# SDC_3.net
KiCad netlist of a schematic drawn in Altium Designer
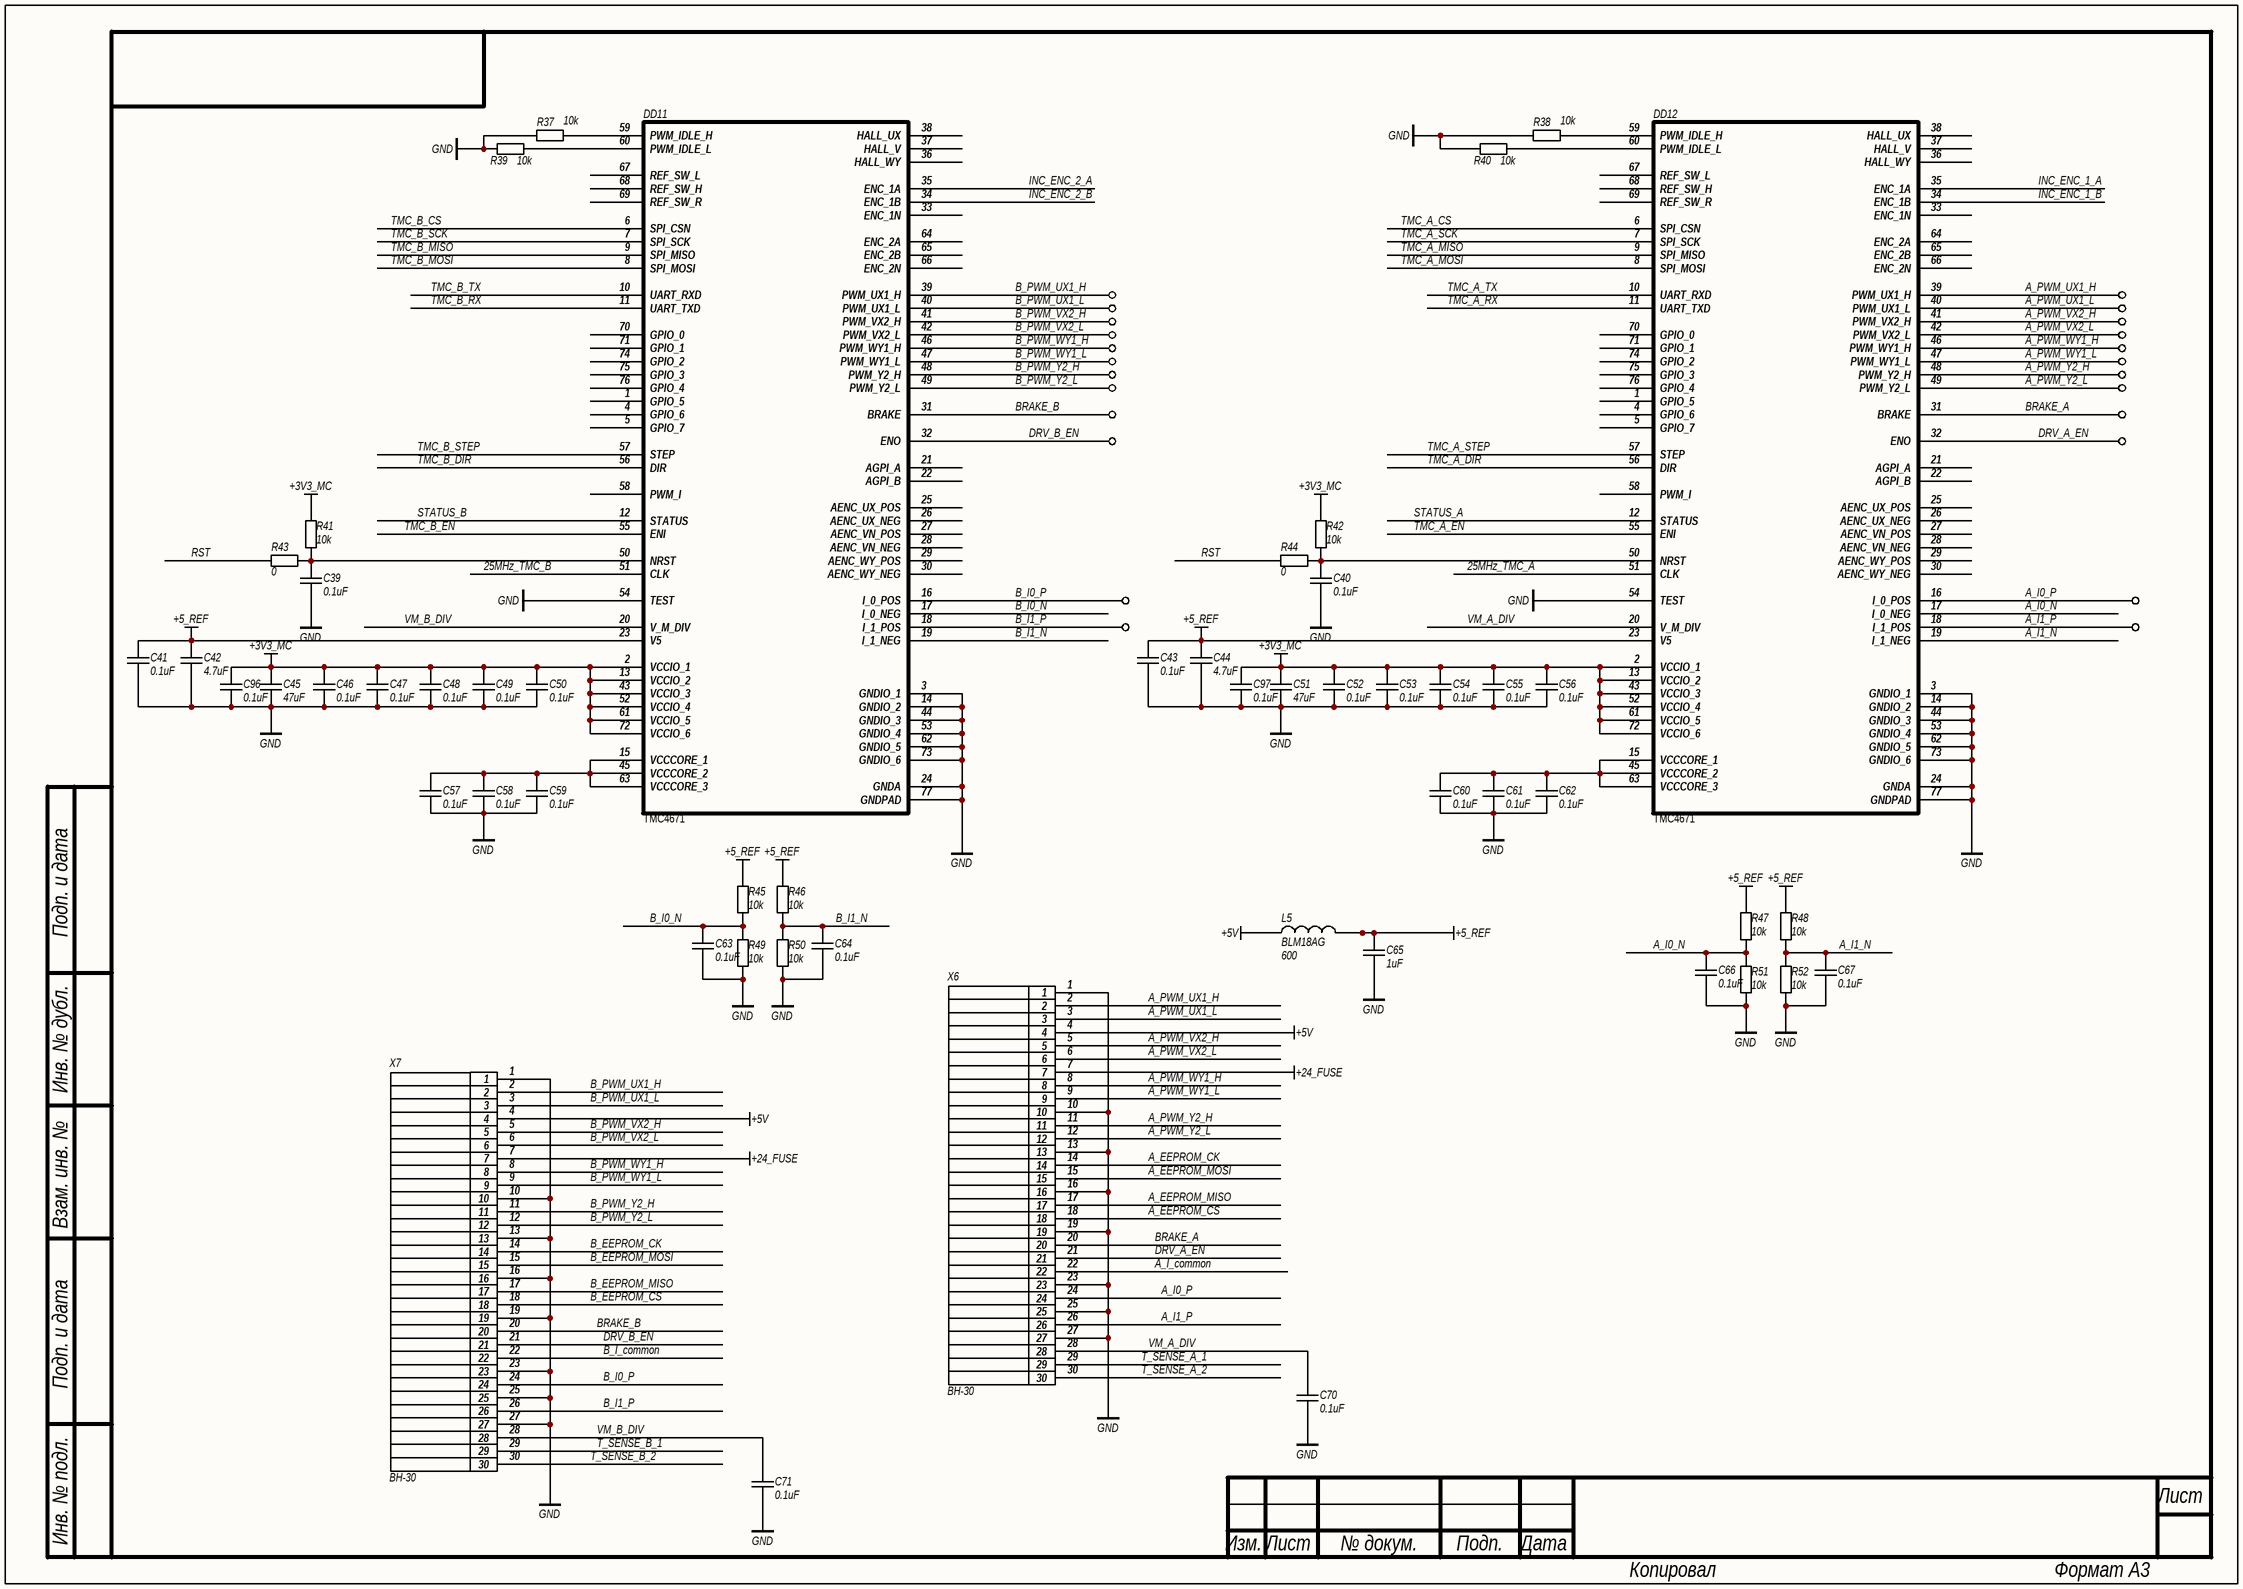
[diagram p0: SDC_3.SchDoc]

(export (version "E")
  (design (tool "Eeschema 10.0.6"))
  (components
    (comp (ref "C39")
      (value "0.1uF")
      (footprint "C0603")
      (description "SMD Capacitor")
      (fields (field (name "MANUFACTURER") "Murata") (field (name "TOLERANCE") "10%"))
      (libsource (lib "VKA") (part "CAP"))
    )
    (comp (ref "C40")
      (value "0.1uF")
      (footprint "C0603")
      (description "SMD Capacitor")
      (fields (field (name "MANUFACTURER") "Murata") (field (name "TOLERANCE") "10%"))
      (libsource (lib "VKA") (part "CAP"))
    )
    (comp (ref "C41")
      (value "0.1uF")
      (footprint "C0603")
      (description "SMD Capacitor")
      (fields (field (name "MANUFACTURER") "Murata") (field (name "TOLERANCE") "10%"))
      (libsource (lib "VKA") (part "CAP"))
    )
    (comp (ref "C42")
      (value "4.7uF")
      (footprint "C0603")
      (description "SMD Capacitor")
      (fields (field (name "MANUFACTURER") "Murata") (field (name "TOLERANCE") "10%"))
      (libsource (lib "VKA") (part "CAP"))
    )
    (comp (ref "C43")
      (value "0.1uF")
      (footprint "C0603")
      (description "SMD Capacitor")
      (fields (field (name "MANUFACTURER") "Murata") (field (name "TOLERANCE") "10%"))
      (libsource (lib "VKA") (part "CAP"))
    )
    (comp (ref "C44")
      (value "4.7uF")
      (footprint "C0603")
      (description "SMD Capacitor")
      (fields (field (name "MANUFACTURER") "Murata") (field (name "TOLERANCE") "10%"))
      (libsource (lib "VKA") (part "CAP"))
    )
    (comp (ref "C45")
      (value "47uF")
      (footprint "C1206")
      (description "SMD Capacitor")
      (fields (field (name "MANUFACTURER") "Murata") (field (name "TOLERANCE") "10%"))
      (libsource (lib "VKA") (part "CAP"))
    )
    (comp (ref "C46")
      (value "0.1uF")
      (footprint "C0603")
      (description "SMD Capacitor")
      (fields (field (name "MANUFACTURER") "Murata") (field (name "TOLERANCE") "10%"))
      (libsource (lib "VKA") (part "CAP"))
    )
    (comp (ref "C47")
      (value "0.1uF")
      (footprint "C0603")
      (description "SMD Capacitor")
      (fields (field (name "MANUFACTURER") "Murata") (field (name "TOLERANCE") "10%"))
      (libsource (lib "VKA") (part "CAP"))
    )
    (comp (ref "C48")
      (value "0.1uF")
      (footprint "C0603")
      (description "SMD Capacitor")
      (fields (field (name "MANUFACTURER") "Murata") (field (name "TOLERANCE") "10%"))
      (libsource (lib "VKA") (part "CAP"))
    )
    (comp (ref "C49")
      (value "0.1uF")
      (footprint "C0603")
      (description "SMD Capacitor")
      (fields (field (name "MANUFACTURER") "Murata") (field (name "TOLERANCE") "10%"))
      (libsource (lib "VKA") (part "CAP"))
    )
    (comp (ref "C50")
      (value "0.1uF")
      (footprint "C0603")
      (description "SMD Capacitor")
      (fields (field (name "MANUFACTURER") "Murata") (field (name "TOLERANCE") "10%"))
      (libsource (lib "VKA") (part "CAP"))
    )
    (comp (ref "C51")
      (value "47uF")
      (footprint "C1206")
      (description "SMD Capacitor")
      (fields (field (name "MANUFACTURER") "Murata") (field (name "TOLERANCE") "10%"))
      (libsource (lib "VKA") (part "CAP"))
    )
    (comp (ref "C52")
      (value "0.1uF")
      (footprint "C0603")
      (description "SMD Capacitor")
      (fields (field (name "MANUFACTURER") "Murata") (field (name "TOLERANCE") "10%"))
      (libsource (lib "VKA") (part "CAP"))
    )
    (comp (ref "C53")
      (value "0.1uF")
      (footprint "C0603")
      (description "SMD Capacitor")
      (fields (field (name "MANUFACTURER") "Murata") (field (name "TOLERANCE") "10%"))
      (libsource (lib "VKA") (part "CAP"))
    )
    (comp (ref "C54")
      (value "0.1uF")
      (footprint "C0603")
      (description "SMD Capacitor")
      (fields (field (name "MANUFACTURER") "Murata") (field (name "TOLERANCE") "10%"))
      (libsource (lib "VKA") (part "CAP"))
    )
    (comp (ref "C55")
      (value "0.1uF")
      (footprint "C0603")
      (description "SMD Capacitor")
      (fields (field (name "MANUFACTURER") "Murata") (field (name "TOLERANCE") "10%"))
      (libsource (lib "VKA") (part "CAP"))
    )
    (comp (ref "C56")
      (value "0.1uF")
      (footprint "C0603")
      (description "SMD Capacitor")
      (fields (field (name "MANUFACTURER") "Murata") (field (name "TOLERANCE") "10%"))
      (libsource (lib "VKA") (part "CAP"))
    )
    (comp (ref "C57")
      (value "0.1uF")
      (footprint "C0603")
      (description "SMD Capacitor")
      (fields (field (name "MANUFACTURER") "Murata") (field (name "TOLERANCE") "10%"))
      (libsource (lib "VKA") (part "CAP"))
    )
    (comp (ref "C58")
      (value "0.1uF")
      (footprint "C0603")
      (description "SMD Capacitor")
      (fields (field (name "MANUFACTURER") "Murata") (field (name "TOLERANCE") "10%"))
      (libsource (lib "VKA") (part "CAP"))
    )
    (comp (ref "C59")
      (value "0.1uF")
      (footprint "C0603")
      (description "SMD Capacitor")
      (fields (field (name "MANUFACTURER") "Murata") (field (name "TOLERANCE") "10%"))
      (libsource (lib "VKA") (part "CAP"))
    )
    (comp (ref "C60")
      (value "0.1uF")
      (footprint "C0603")
      (description "SMD Capacitor")
      (fields (field (name "MANUFACTURER") "Murata") (field (name "TOLERANCE") "10%"))
      (libsource (lib "VKA") (part "CAP"))
    )
    (comp (ref "C61")
      (value "0.1uF")
      (footprint "C0603")
      (description "SMD Capacitor")
      (fields (field (name "MANUFACTURER") "Murata") (field (name "TOLERANCE") "10%"))
      (libsource (lib "VKA") (part "CAP"))
    )
    (comp (ref "C62")
      (value "0.1uF")
      (footprint "C0603")
      (description "SMD Capacitor")
      (fields (field (name "MANUFACTURER") "Murata") (field (name "TOLERANCE") "10%"))
      (libsource (lib "VKA") (part "CAP"))
    )
    (comp (ref "C63")
      (value "0.1uF")
      (footprint "C0603")
      (description "SMD Capacitor")
      (fields (field (name "MANUFACTURER") "Murata") (field (name "TOLERANCE") "10%"))
      (libsource (lib "VKA") (part "CAP"))
    )
    (comp (ref "C64")
      (value "0.1uF")
      (footprint "C0603")
      (description "SMD Capacitor")
      (fields (field (name "MANUFACTURER") "Murata") (field (name "TOLERANCE") "10%"))
      (libsource (lib "VKA") (part "CAP"))
    )
    (comp (ref "C65")
      (value "1uF")
      (footprint "C0603")
      (description "SMD Capacitor")
      (fields (field (name "MANUFACTURER") "Murata") (field (name "TOLERANCE") "10%"))
      (libsource (lib "VKA") (part "CAP"))
    )
    (comp (ref "C66")
      (value "0.1uF")
      (footprint "C0603")
      (description "SMD Capacitor")
      (fields (field (name "MANUFACTURER") "Murata") (field (name "TOLERANCE") "10%"))
      (libsource (lib "VKA") (part "CAP"))
    )
    (comp (ref "C67")
      (value "0.1uF")
      (footprint "C0603")
      (description "SMD Capacitor")
      (fields (field (name "MANUFACTURER") "Murata") (field (name "TOLERANCE") "10%"))
      (libsource (lib "VKA") (part "CAP"))
    )
    (comp (ref "C70")
      (value "0.1uF")
      (footprint "C0603")
      (description "SMD Capacitor")
      (fields (field (name "MANUFACTURER") "Murata") (field (name "TOLERANCE") "10%"))
      (libsource (lib "VKA") (part "CAP"))
    )
    (comp (ref "C71")
      (value "0.1uF")
      (footprint "C0603")
      (description "SMD Capacitor")
      (fields (field (name "MANUFACTURER") "Murata") (field (name "TOLERANCE") "10%"))
      (libsource (lib "VKA") (part "CAP"))
    )
    (comp (ref "C96")
      (value "0.1uF")
      (footprint "C0603")
      (description "SMD Capacitor")
      (fields (field (name "MANUFACTURER") "Murata") (field (name "TOLERANCE") "10%"))
      (libsource (lib "VKA") (part "CAP"))
    )
    (comp (ref "C97")
      (value "0.1uF")
      (footprint "C0603")
      (description "SMD Capacitor")
      (fields (field (name "MANUFACTURER") "Murata") (field (name "TOLERANCE") "10%"))
      (libsource (lib "VKA") (part "CAP"))
    )
    (comp (ref "DD11")
      (value "TMC4671")
      (footprint "QFN76")
      (description "Motion_controller")
      (libsource (lib "VKA") (part "TMC4671"))
    )
    (comp (ref "DD12")
      (value "TMC4671")
      (footprint "QFN76")
      (description "Motion_controller")
      (libsource (lib "VKA") (part "TMC4671"))
    )
    (comp (ref "L5")
      (value "BLM18AG")
      (footprint "R0603")
      (fields (field (name "ALTIUM_VALUE") "600"))
      (libsource (lib "VKA") (part "BLM18AG"))
    )
    (comp (ref "R37")
      (value "10k")
      (footprint "R0603")
      (description "SMD Resistor")
      (fields (field (name "POWER") "0.062 Wt") (field (name "TOLERANCE") "5%"))
      (libsource (lib "VKA") (part "RES"))
    )
    (comp (ref "R38")
      (value "10k")
      (footprint "R0603")
      (description "SMD Resistor")
      (fields (field (name "POWER") "0.062 Wt") (field (name "TOLERANCE") "5%"))
      (libsource (lib "VKA") (part "RES"))
    )
    (comp (ref "R39")
      (value "10k")
      (footprint "R0603")
      (description "SMD Resistor")
      (fields (field (name "POWER") "0.062 Wt") (field (name "TOLERANCE") "5%"))
      (libsource (lib "VKA") (part "RES"))
    )
    (comp (ref "R40")
      (value "10k")
      (footprint "R0603")
      (description "SMD Resistor")
      (fields (field (name "POWER") "0.062 Wt") (field (name "TOLERANCE") "5%"))
      (libsource (lib "VKA") (part "RES"))
    )
    (comp (ref "R41")
      (value "10k")
      (footprint "R0603")
      (description "SMD Resistor")
      (fields (field (name "POWER") "0.062 Wt") (field (name "TOLERANCE") "5%"))
      (libsource (lib "") (part "RES_1"))
    )
    (comp (ref "R42")
      (value "10k")
      (footprint "R0603")
      (description "SMD Resistor")
      (fields (field (name "POWER") "0.062 Wt") (field (name "TOLERANCE") "5%"))
      (libsource (lib "") (part "RES_1"))
    )
    (comp (ref "R43")
      (value "0")
      (footprint "R0603")
      (description "SMD Resistor")
      (fields (field (name "POWER") "0.062 Wt") (field (name "TOLERANCE") "5%"))
      (libsource (lib "VKA") (part "RES"))
    )
    (comp (ref "R44")
      (value "0")
      (footprint "R0603")
      (description "SMD Resistor")
      (fields (field (name "POWER") "0.062 Wt") (field (name "TOLERANCE") "5%"))
      (libsource (lib "VKA") (part "RES"))
    )
    (comp (ref "R45")
      (value "10k")
      (footprint "R0603")
      (description "SMD Resistor")
      (fields (field (name "POWER") "0.062 Wt") (field (name "TOLERANCE") "5%"))
      (libsource (lib "") (part "RES_1"))
    )
    (comp (ref "R46")
      (value "10k")
      (footprint "R0603")
      (description "SMD Resistor")
      (fields (field (name "POWER") "0.062 Wt") (field (name "TOLERANCE") "5%"))
      (libsource (lib "") (part "RES_1"))
    )
    (comp (ref "R47")
      (value "10k")
      (footprint "R0603")
      (description "SMD Resistor")
      (fields (field (name "POWER") "0.062 Wt") (field (name "TOLERANCE") "5%"))
      (libsource (lib "") (part "RES_1"))
    )
    (comp (ref "R48")
      (value "10k")
      (footprint "R0603")
      (description "SMD Resistor")
      (fields (field (name "POWER") "0.062 Wt") (field (name "TOLERANCE") "5%"))
      (libsource (lib "") (part "RES_1"))
    )
    (comp (ref "R49")
      (value "10k")
      (footprint "R0603")
      (description "SMD Resistor")
      (fields (field (name "POWER") "0.062 Wt") (field (name "TOLERANCE") "5%"))
      (libsource (lib "") (part "RES_1"))
    )
    (comp (ref "R50")
      (value "10k")
      (footprint "R0603")
      (description "SMD Resistor")
      (fields (field (name "POWER") "0.062 Wt") (field (name "TOLERANCE") "5%"))
      (libsource (lib "") (part "RES_1"))
    )
    (comp (ref "R51")
      (value "10k")
      (footprint "R0603")
      (description "SMD Resistor")
      (fields (field (name "POWER") "0.062 Wt") (field (name "TOLERANCE") "5%"))
      (libsource (lib "") (part "RES_1"))
    )
    (comp (ref "R52")
      (value "10k")
      (footprint "R0603")
      (description "SMD Resistor")
      (fields (field (name "POWER") "0.062 Wt") (field (name "TOLERANCE") "5%"))
      (libsource (lib "") (part "RES_1"))
    )
    (comp (ref "TP1") (value "Test_point") (footprint "TP1") (libsource (lib "VKA") (part "TP")))
    (comp (ref "TP2") (value "Test_point") (footprint "TP1") (libsource (lib "VKA") (part "TP")))
    (comp (ref "TP3") (value "Test_point") (footprint "TP1") (libsource (lib "VKA") (part "TP")))
    (comp (ref "TP4") (value "Test_point") (footprint "TP1") (libsource (lib "VKA") (part "TP")))
    (comp (ref "TP5") (value "Test_point") (footprint "TP1") (libsource (lib "VKA") (part "TP")))
    (comp (ref "TP6") (value "Test_point") (footprint "TP1") (libsource (lib "VKA") (part "TP")))
    (comp (ref "TP7") (value "Test_point") (footprint "TP1") (libsource (lib "VKA") (part "TP")))
    (comp (ref "TP8") (value "Test_point") (footprint "TP1") (libsource (lib "VKA") (part "TP")))
    (comp (ref "TP9") (value "Test_point") (footprint "TP1") (libsource (lib "VKA") (part "TP")))
    (comp (ref "TP10") (value "Test_point") (footprint "TP1") (libsource (lib "VKA") (part "TP")))
    (comp (ref "TP11") (value "Test_point") (footprint "TP1") (libsource (lib "VKA") (part "TP")))
    (comp (ref "TP12") (value "Test_point") (footprint "TP1") (libsource (lib "VKA") (part "TP")))
    (comp (ref "TP13") (value "Test_point") (footprint "TP1") (libsource (lib "VKA") (part "TP")))
    (comp (ref "TP14") (value "Test_point") (footprint "TP1") (libsource (lib "VKA") (part "TP")))
    (comp (ref "TP15") (value "Test_point") (footprint "TP1") (libsource (lib "VKA") (part "TP")))
    (comp (ref "TP16") (value "Test_point") (footprint "TP1") (libsource (lib "VKA") (part "TP")))
    (comp (ref "TP17") (value "Test_point") (footprint "TP1") (libsource (lib "VKA") (part "TP")))
    (comp (ref "TP18") (value "Test_point") (footprint "TP1") (libsource (lib "VKA") (part "TP")))
    (comp (ref "TP19") (value "Test_point") (footprint "TP1") (libsource (lib "VKA") (part "TP")))
    (comp (ref "TP20") (value "Test_point") (footprint "TP1") (libsource (lib "VKA") (part "TP")))
    (comp (ref "TP21") (value "Test_point") (footprint "TP1") (libsource (lib "VKA") (part "TP")))
    (comp (ref "TP22") (value "Test_point") (footprint "TP1") (libsource (lib "VKA") (part "TP")))
    (comp (ref "TP23") (value "Test_point") (footprint "TP1") (libsource (lib "VKA") (part "TP")))
    (comp (ref "TP24") (value "Test_point") (footprint "TP1") (libsource (lib "VKA") (part "TP")))
    (comp (ref "X6")
      (value "BH-30")
      (footprint "IDC-30(BH-30)")
      (libsource (lib "VKA") (part "IDC15x2_GOST"))
    )
    (comp (ref "X7")
      (value "BH-30")
      (footprint "IDC-30(BH-30)")
      (libsource (lib "VKA") (part "IDC15x2_GOST"))
    )
  )
  (nets
    (net (code "1") (name "+3V3_MC") (class "Default")
      (node (ref "C45") (pin "2") (pinfunction "2_2") (pintype "passive"))
      (node (ref "C46") (pin "2") (pinfunction "2_2") (pintype "passive"))
      (node (ref "C47") (pin "2") (pinfunction "2_2") (pintype "passive"))
      (node (ref "C48") (pin "2") (pinfunction "2_2") (pintype "passive"))
      (node (ref "C49") (pin "2") (pinfunction "2_2") (pintype "passive"))
      (node (ref "C50") (pin "2") (pinfunction "2_2") (pintype "passive"))
      (node (ref "C51") (pin "2") (pinfunction "2_2") (pintype "passive"))
      (node (ref "C52") (pin "2") (pinfunction "2_2") (pintype "passive"))
      (node (ref "C53") (pin "2") (pinfunction "2_2") (pintype "passive"))
      (node (ref "C54") (pin "2") (pinfunction "2_2") (pintype "passive"))
      (node (ref "C55") (pin "2") (pinfunction "2_2") (pintype "passive"))
      (node (ref "C56") (pin "2") (pinfunction "2_2") (pintype "passive"))
      (node (ref "C96") (pin "2") (pinfunction "2_2") (pintype "passive"))
      (node (ref "C97") (pin "2") (pinfunction "2_2") (pintype "passive"))
      (node (ref "DD11") (pin "13") (pinfunction "VCCIO_2_13") (pintype "passive"))
      (node (ref "DD11") (pin "2") (pinfunction "VCCIO_1_2") (pintype "passive"))
      (node (ref "DD11") (pin "43") (pinfunction "VCCIO_3_43") (pintype "passive"))
      (node (ref "DD11") (pin "52") (pinfunction "VCCIO_4_52") (pintype "passive"))
      (node (ref "DD11") (pin "61") (pinfunction "VCCIO_5_61") (pintype "passive"))
      (node (ref "DD11") (pin "72") (pinfunction "VCCIO_6_72") (pintype "passive"))
      (node (ref "DD12") (pin "13") (pinfunction "VCCIO_2_13") (pintype "passive"))
      (node (ref "DD12") (pin "2") (pinfunction "VCCIO_1_2") (pintype "passive"))
      (node (ref "DD12") (pin "43") (pinfunction "VCCIO_3_43") (pintype "passive"))
      (node (ref "DD12") (pin "52") (pinfunction "VCCIO_4_52") (pintype "passive"))
      (node (ref "DD12") (pin "61") (pinfunction "VCCIO_5_61") (pintype "passive"))
      (node (ref "DD12") (pin "72") (pinfunction "VCCIO_6_72") (pintype "passive"))
      (node (ref "R41") (pin "2") (pinfunction "2_2") (pintype "passive"))
      (node (ref "R42") (pin "2") (pinfunction "2_2") (pintype "passive"))
    )
    (net (code "2") (name "+5V") (class "Default")
      (node (ref "L5") (pin "1") (pinfunction "1_1") (pintype "passive"))
      (node (ref "X6") (pin "4") (pinfunction "4_4") (pintype "passive"))
      (node (ref "X7") (pin "4") (pinfunction "4_4") (pintype "passive"))
    )
    (net (code "3") (name "+5_REF") (class "Default")
      (node (ref "C41") (pin "2") (pinfunction "2_2") (pintype "passive"))
      (node (ref "C42") (pin "2") (pinfunction "2_2") (pintype "passive"))
      (node (ref "C43") (pin "2") (pinfunction "2_2") (pintype "passive"))
      (node (ref "C44") (pin "2") (pinfunction "2_2") (pintype "passive"))
      (node (ref "C65") (pin "2") (pinfunction "2_2") (pintype "passive"))
      (node (ref "DD11") (pin "23") (pinfunction "V5_23") (pintype "passive"))
      (node (ref "DD12") (pin "23") (pinfunction "V5_23") (pintype "passive"))
      (node (ref "L5") (pin "2") (pinfunction "2_2") (pintype "passive"))
      (node (ref "R45") (pin "2") (pinfunction "2_2") (pintype "passive"))
      (node (ref "R46") (pin "2") (pinfunction "2_2") (pintype "passive"))
      (node (ref "R47") (pin "2") (pinfunction "2_2") (pintype "passive"))
      (node (ref "R48") (pin "2") (pinfunction "2_2") (pintype "passive"))
    )
    (net (code "4") (name "+24_FUSE") (class "Default")
      (node (ref "X6") (pin "7") (pinfunction "7_7") (pintype "passive"))
      (node (ref "X7") (pin "7") (pinfunction "7_7") (pintype "passive"))
    )
    (net (code "5") (name "/25MHz_TMC_A") (class "Default")
      (node (ref "DD12") (pin "51") (pinfunction "CLK_51") (pintype "passive"))
    )
    (net (code "6") (name "/25MHz_TMC_B") (class "Default")
      (node (ref "DD11") (pin "51") (pinfunction "CLK_51") (pintype "passive"))
    )
    (net (code "7") (name "/A_EEPROM_CK") (class "Default")
      (node (ref "X6") (pin "14") (pinfunction "14_14") (pintype "passive"))
    )
    (net (code "8") (name "/A_EEPROM_CS") (class "Default")
      (node (ref "X6") (pin "18") (pinfunction "18_18") (pintype "passive"))
    )
    (net (code "9") (name "/A_EEPROM_MISO") (class "Default")
      (node (ref "X6") (pin "17") (pinfunction "17_17") (pintype "passive"))
    )
    (net (code "10") (name "/A_EEPROM_MOSI") (class "Default")
      (node (ref "X6") (pin "15") (pinfunction "15_15") (pintype "passive"))
    )
    (net (code "11") (name "/A_I0_N") (class "Default")
      (node (ref "C66") (pin "2") (pinfunction "2_2") (pintype "passive"))
      (node (ref "DD12") (pin "17") (pinfunction "I_0_NEG_17") (pintype "passive"))
      (node (ref "R47") (pin "1") (pinfunction "1_1") (pintype "passive"))
      (node (ref "R51") (pin "2") (pinfunction "2_2") (pintype "passive"))
    )
    (net (code "12") (name "/A_I0_P") (class "Default")
      (node (ref "DD12") (pin "16") (pinfunction "I_0_POS_16") (pintype "passive"))
      (node (ref "TP23") (pin "1") (pinfunction "1_1") (pintype "passive"))
      (node (ref "X6") (pin "24") (pinfunction "24_24") (pintype "passive"))
    )
    (net (code "13") (name "/A_I1_N") (class "Default")
      (node (ref "C67") (pin "2") (pinfunction "2_2") (pintype "passive"))
      (node (ref "DD12") (pin "19") (pinfunction "I_1_NEG_19") (pintype "passive"))
      (node (ref "R48") (pin "1") (pinfunction "1_1") (pintype "passive"))
      (node (ref "R52") (pin "2") (pinfunction "2_2") (pintype "passive"))
    )
    (net (code "14") (name "/A_I1_P") (class "Default")
      (node (ref "DD12") (pin "18") (pinfunction "I_1_POS_18") (pintype "passive"))
      (node (ref "TP24") (pin "1") (pinfunction "1_1") (pintype "passive"))
      (node (ref "X6") (pin "26") (pinfunction "26_26") (pintype "passive"))
    )
    (net (code "15") (name "/A_I_common") (class "Default")
      (node (ref "X6") (pin "22") (pinfunction "22_22") (pintype "passive"))
    )
    (net (code "16") (name "/A_PWM_UX1_H") (class "Default")
      (node (ref "DD12") (pin "39") (pinfunction "PWM_UX1_H_39") (pintype "passive"))
      (node (ref "TP2") (pin "1") (pinfunction "1_1") (pintype "passive"))
      (node (ref "X6") (pin "2") (pinfunction "2_2") (pintype "passive"))
    )
    (net (code "17") (name "/A_PWM_UX1_L") (class "Default")
      (node (ref "DD12") (pin "40") (pinfunction "PWM_UX1_L_40") (pintype "passive"))
      (node (ref "TP4") (pin "1") (pinfunction "1_1") (pintype "passive"))
      (node (ref "X6") (pin "3") (pinfunction "3_3") (pintype "passive"))
    )
    (net (code "18") (name "/A_PWM_VX2_H") (class "Default")
      (node (ref "DD12") (pin "41") (pinfunction "PWM_VX2_H_41") (pintype "passive"))
      (node (ref "TP6") (pin "1") (pinfunction "1_1") (pintype "passive"))
      (node (ref "X6") (pin "5") (pinfunction "5_5") (pintype "passive"))
    )
    (net (code "19") (name "/A_PWM_VX2_L") (class "Default")
      (node (ref "DD12") (pin "42") (pinfunction "PWM_VX2_L_42") (pintype "passive"))
      (node (ref "TP8") (pin "1") (pinfunction "1_1") (pintype "passive"))
      (node (ref "X6") (pin "6") (pinfunction "6_6") (pintype "passive"))
    )
    (net (code "20") (name "/A_PWM_WY1_H") (class "Default")
      (node (ref "DD12") (pin "46") (pinfunction "PWM_WY1_H_46") (pintype "passive"))
      (node (ref "TP10") (pin "1") (pinfunction "1_1") (pintype "passive"))
      (node (ref "X6") (pin "8") (pinfunction "8_8") (pintype "passive"))
    )
    (net (code "21") (name "/A_PWM_WY1_L") (class "Default")
      (node (ref "DD12") (pin "47") (pinfunction "PWM_WY1_L_47") (pintype "passive"))
      (node (ref "TP12") (pin "1") (pinfunction "1_1") (pintype "passive"))
      (node (ref "X6") (pin "9") (pinfunction "9_9") (pintype "passive"))
    )
    (net (code "22") (name "/A_PWM_Y2_H") (class "Default")
      (node (ref "DD12") (pin "48") (pinfunction "PWM_Y2_H_48") (pintype "passive"))
      (node (ref "TP14") (pin "1") (pinfunction "1_1") (pintype "passive"))
      (node (ref "X6") (pin "11") (pinfunction "11_11") (pintype "passive"))
    )
    (net (code "23") (name "/A_PWM_Y2_L") (class "Default")
      (node (ref "DD12") (pin "49") (pinfunction "PWM_Y2_L_49") (pintype "passive"))
      (node (ref "TP16") (pin "1") (pinfunction "1_1") (pintype "passive"))
      (node (ref "X6") (pin "12") (pinfunction "12_12") (pintype "passive"))
    )
    (net (code "24") (name "/BRAKE_A") (class "Default")
      (node (ref "DD12") (pin "31") (pinfunction "BRAKE_31") (pintype "passive"))
      (node (ref "TP22") (pin "1") (pinfunction "1_1") (pintype "passive"))
      (node (ref "X6") (pin "20") (pinfunction "20_20") (pintype "passive"))
    )
    (net (code "25") (name "/BRAKE_B") (class "Default")
      (node (ref "DD11") (pin "31") (pinfunction "BRAKE_31") (pintype "passive"))
      (node (ref "TP21") (pin "1") (pinfunction "1_1") (pintype "passive"))
      (node (ref "X7") (pin "20") (pinfunction "20_20") (pintype "passive"))
    )
    (net (code "26") (name "/B_EEPROM_CK") (class "Default")
      (node (ref "X7") (pin "14") (pinfunction "14_14") (pintype "passive"))
    )
    (net (code "27") (name "/B_EEPROM_CS") (class "Default")
      (node (ref "X7") (pin "18") (pinfunction "18_18") (pintype "passive"))
    )
    (net (code "28") (name "/B_EEPROM_MISO") (class "Default")
      (node (ref "X7") (pin "17") (pinfunction "17_17") (pintype "passive"))
    )
    (net (code "29") (name "/B_EEPROM_MOSI") (class "Default")
      (node (ref "X7") (pin "15") (pinfunction "15_15") (pintype "passive"))
    )
    (net (code "30") (name "/B_I0_N") (class "Default")
      (node (ref "C63") (pin "2") (pinfunction "2_2") (pintype "passive"))
      (node (ref "DD11") (pin "17") (pinfunction "I_0_NEG_17") (pintype "passive"))
      (node (ref "R45") (pin "1") (pinfunction "1_1") (pintype "passive"))
      (node (ref "R49") (pin "2") (pinfunction "2_2") (pintype "passive"))
    )
    (net (code "31") (name "/B_I0_P") (class "Default")
      (node (ref "DD11") (pin "16") (pinfunction "I_0_POS_16") (pintype "passive"))
      (node (ref "TP19") (pin "1") (pinfunction "1_1") (pintype "passive"))
      (node (ref "X7") (pin "24") (pinfunction "24_24") (pintype "passive"))
    )
    (net (code "32") (name "/B_I1_N") (class "Default")
      (node (ref "C64") (pin "2") (pinfunction "2_2") (pintype "passive"))
      (node (ref "DD11") (pin "19") (pinfunction "I_1_NEG_19") (pintype "passive"))
      (node (ref "R46") (pin "1") (pinfunction "1_1") (pintype "passive"))
      (node (ref "R50") (pin "2") (pinfunction "2_2") (pintype "passive"))
    )
    (net (code "33") (name "/B_I1_P") (class "Default")
      (node (ref "DD11") (pin "18") (pinfunction "I_1_POS_18") (pintype "passive"))
      (node (ref "TP20") (pin "1") (pinfunction "1_1") (pintype "passive"))
      (node (ref "X7") (pin "26") (pinfunction "26_26") (pintype "passive"))
    )
    (net (code "34") (name "/B_I_common") (class "Default")
      (node (ref "X7") (pin "22") (pinfunction "22_22") (pintype "passive"))
    )
    (net (code "35") (name "/B_PWM_UX1_H") (class "Default")
      (node (ref "DD11") (pin "39") (pinfunction "PWM_UX1_H_39") (pintype "passive"))
      (node (ref "TP1") (pin "1") (pinfunction "1_1") (pintype "passive"))
      (node (ref "X7") (pin "2") (pinfunction "2_2") (pintype "passive"))
    )
    (net (code "36") (name "/B_PWM_UX1_L") (class "Default")
      (node (ref "DD11") (pin "40") (pinfunction "PWM_UX1_L_40") (pintype "passive"))
      (node (ref "TP3") (pin "1") (pinfunction "1_1") (pintype "passive"))
      (node (ref "X7") (pin "3") (pinfunction "3_3") (pintype "passive"))
    )
    (net (code "37") (name "/B_PWM_VX2_H") (class "Default")
      (node (ref "DD11") (pin "41") (pinfunction "PWM_VX2_H_41") (pintype "passive"))
      (node (ref "TP5") (pin "1") (pinfunction "1_1") (pintype "passive"))
      (node (ref "X7") (pin "5") (pinfunction "5_5") (pintype "passive"))
    )
    (net (code "38") (name "/B_PWM_VX2_L") (class "Default")
      (node (ref "DD11") (pin "42") (pinfunction "PWM_VX2_L_42") (pintype "passive"))
      (node (ref "TP7") (pin "1") (pinfunction "1_1") (pintype "passive"))
      (node (ref "X7") (pin "6") (pinfunction "6_6") (pintype "passive"))
    )
    (net (code "39") (name "/B_PWM_WY1_H") (class "Default")
      (node (ref "DD11") (pin "46") (pinfunction "PWM_WY1_H_46") (pintype "passive"))
      (node (ref "TP9") (pin "1") (pinfunction "1_1") (pintype "passive"))
      (node (ref "X7") (pin "8") (pinfunction "8_8") (pintype "passive"))
    )
    (net (code "40") (name "/B_PWM_WY1_L") (class "Default")
      (node (ref "DD11") (pin "47") (pinfunction "PWM_WY1_L_47") (pintype "passive"))
      (node (ref "TP11") (pin "1") (pinfunction "1_1") (pintype "passive"))
      (node (ref "X7") (pin "9") (pinfunction "9_9") (pintype "passive"))
    )
    (net (code "41") (name "/B_PWM_Y2_H") (class "Default")
      (node (ref "DD11") (pin "48") (pinfunction "PWM_Y2_H_48") (pintype "passive"))
      (node (ref "TP13") (pin "1") (pinfunction "1_1") (pintype "passive"))
      (node (ref "X7") (pin "11") (pinfunction "11_11") (pintype "passive"))
    )
    (net (code "42") (name "/B_PWM_Y2_L") (class "Default")
      (node (ref "DD11") (pin "49") (pinfunction "PWM_Y2_L_49") (pintype "passive"))
      (node (ref "TP15") (pin "1") (pinfunction "1_1") (pintype "passive"))
      (node (ref "X7") (pin "12") (pinfunction "12_12") (pintype "passive"))
    )
    (net (code "43") (name "/DRV_A_EN") (class "Default")
      (node (ref "DD12") (pin "32") (pinfunction "ENO_32") (pintype "passive"))
      (node (ref "TP18") (pin "1") (pinfunction "1_1") (pintype "passive"))
      (node (ref "X6") (pin "21") (pinfunction "21_21") (pintype "passive"))
    )
    (net (code "44") (name "/DRV_B_EN") (class "Default")
      (node (ref "DD11") (pin "32") (pinfunction "ENO_32") (pintype "passive"))
      (node (ref "TP17") (pin "1") (pinfunction "1_1") (pintype "passive"))
      (node (ref "X7") (pin "21") (pinfunction "21_21") (pintype "passive"))
    )
    (net (code "45") (name "/INC_ENC_1_A") (class "Default")
      (node (ref "DD12") (pin "35") (pinfunction "ENC_1A_35") (pintype "passive"))
    )
    (net (code "46") (name "/INC_ENC_1_B") (class "Default")
      (node (ref "DD12") (pin "34") (pinfunction "ENC_1B_34") (pintype "passive"))
    )
    (net (code "47") (name "/INC_ENC_2_A") (class "Default")
      (node (ref "DD11") (pin "35") (pinfunction "ENC_1A_35") (pintype "passive"))
    )
    (net (code "48") (name "/INC_ENC_2_B") (class "Default")
      (node (ref "DD11") (pin "34") (pinfunction "ENC_1B_34") (pintype "passive"))
    )
    (net (code "49") (name "/RST") (class "Default")
      (node (ref "R43") (pin "2") (pinfunction "2_2") (pintype "passive"))
      (node (ref "R44") (pin "2") (pinfunction "2_2") (pintype "passive"))
    )
    (net (code "50") (name "/STATUS_A") (class "Default")
      (node (ref "DD12") (pin "12") (pinfunction "STATUS_12") (pintype "passive"))
    )
    (net (code "51") (name "/STATUS_B") (class "Default")
      (node (ref "DD11") (pin "12") (pinfunction "STATUS_12") (pintype "passive"))
    )
    (net (code "52") (name "/TMC_A_CS") (class "Default")
      (node (ref "DD12") (pin "6") (pinfunction "SPI_CSN_6") (pintype "passive"))
    )
    (net (code "53") (name "/TMC_A_DIR") (class "Default")
      (node (ref "DD12") (pin "56") (pinfunction "DIR_56") (pintype "passive"))
    )
    (net (code "54") (name "/TMC_A_EN") (class "Default")
      (node (ref "DD12") (pin "55") (pinfunction "ENI_55") (pintype "passive"))
    )
    (net (code "55") (name "/TMC_A_MISO") (class "Default")
      (node (ref "DD12") (pin "9") (pinfunction "SPI_MISO_9") (pintype "passive"))
    )
    (net (code "56") (name "/TMC_A_MOSI") (class "Default")
      (node (ref "DD12") (pin "8") (pinfunction "SPI_MOSI_8") (pintype "passive"))
    )
    (net (code "57") (name "/TMC_A_RX") (class "Default")
      (node (ref "DD12") (pin "11") (pinfunction "UART_TXD_11") (pintype "passive"))
    )
    (net (code "58") (name "/TMC_A_SCK") (class "Default")
      (node (ref "DD12") (pin "7") (pinfunction "SPI_SCK_7") (pintype "passive"))
    )
    (net (code "59") (name "/TMC_A_STEP") (class "Default")
      (node (ref "DD12") (pin "57") (pinfunction "STEP_57") (pintype "passive"))
    )
    (net (code "60") (name "/TMC_A_TX") (class "Default")
      (node (ref "DD12") (pin "10") (pinfunction "UART_RXD_10") (pintype "passive"))
    )
    (net (code "61") (name "/TMC_B_CS") (class "Default")
      (node (ref "DD11") (pin "6") (pinfunction "SPI_CSN_6") (pintype "passive"))
    )
    (net (code "62") (name "/TMC_B_DIR") (class "Default")
      (node (ref "DD11") (pin "56") (pinfunction "DIR_56") (pintype "passive"))
    )
    (net (code "63") (name "/TMC_B_EN") (class "Default")
      (node (ref "DD11") (pin "55") (pinfunction "ENI_55") (pintype "passive"))
    )
    (net (code "64") (name "/TMC_B_MISO") (class "Default")
      (node (ref "DD11") (pin "9") (pinfunction "SPI_MISO_9") (pintype "passive"))
    )
    (net (code "65") (name "/TMC_B_MOSI") (class "Default")
      (node (ref "DD11") (pin "8") (pinfunction "SPI_MOSI_8") (pintype "passive"))
    )
    (net (code "66") (name "/TMC_B_RX") (class "Default")
      (node (ref "DD11") (pin "11") (pinfunction "UART_TXD_11") (pintype "passive"))
    )
    (net (code "67") (name "/TMC_B_SCK") (class "Default")
      (node (ref "DD11") (pin "7") (pinfunction "SPI_SCK_7") (pintype "passive"))
    )
    (net (code "68") (name "/TMC_B_STEP") (class "Default")
      (node (ref "DD11") (pin "57") (pinfunction "STEP_57") (pintype "passive"))
    )
    (net (code "69") (name "/TMC_B_TX") (class "Default")
      (node (ref "DD11") (pin "10") (pinfunction "UART_RXD_10") (pintype "passive"))
    )
    (net (code "70") (name "/T_SENSE_A_1") (class "Default")
      (node (ref "X6") (pin "29") (pinfunction "29_29") (pintype "passive"))
    )
    (net (code "71") (name "/T_SENSE_A_2") (class "Default")
      (node (ref "X6") (pin "30") (pinfunction "30_30") (pintype "passive"))
    )
    (net (code "72") (name "/T_SENSE_B_1") (class "Default")
      (node (ref "X7") (pin "29") (pinfunction "29_29") (pintype "passive"))
    )
    (net (code "73") (name "/T_SENSE_B_2") (class "Default")
      (node (ref "X7") (pin "30") (pinfunction "30_30") (pintype "passive"))
    )
    (net (code "74") (name "/VM_A_DIV") (class "Default")
      (node (ref "C70") (pin "2") (pinfunction "2_2") (pintype "passive"))
      (node (ref "DD12") (pin "20") (pinfunction "V_M_DIV_20") (pintype "passive"))
      (node (ref "X6") (pin "28") (pinfunction "28_28") (pintype "passive"))
    )
    (net (code "75") (name "/VM_B_DIV") (class "Default")
      (node (ref "C71") (pin "2") (pinfunction "2_2") (pintype "passive"))
      (node (ref "DD11") (pin "20") (pinfunction "V_M_DIV_20") (pintype "passive"))
      (node (ref "X7") (pin "28") (pinfunction "28_28") (pintype "passive"))
    )
    (net (code "76") (name "GND") (class "Default")
      (node (ref "C39") (pin "1") (pinfunction "1_1") (pintype "passive"))
      (node (ref "C40") (pin "1") (pinfunction "1_1") (pintype "passive"))
      (node (ref "C41") (pin "1") (pinfunction "1_1") (pintype "passive"))
      (node (ref "C42") (pin "1") (pinfunction "1_1") (pintype "passive"))
      (node (ref "C43") (pin "1") (pinfunction "1_1") (pintype "passive"))
      (node (ref "C44") (pin "1") (pinfunction "1_1") (pintype "passive"))
      (node (ref "C45") (pin "1") (pinfunction "1_1") (pintype "passive"))
      (node (ref "C46") (pin "1") (pinfunction "1_1") (pintype "passive"))
      (node (ref "C47") (pin "1") (pinfunction "1_1") (pintype "passive"))
      (node (ref "C48") (pin "1") (pinfunction "1_1") (pintype "passive"))
      (node (ref "C49") (pin "1") (pinfunction "1_1") (pintype "passive"))
      (node (ref "C50") (pin "1") (pinfunction "1_1") (pintype "passive"))
      (node (ref "C51") (pin "1") (pinfunction "1_1") (pintype "passive"))
      (node (ref "C52") (pin "1") (pinfunction "1_1") (pintype "passive"))
      (node (ref "C53") (pin "1") (pinfunction "1_1") (pintype "passive"))
      (node (ref "C54") (pin "1") (pinfunction "1_1") (pintype "passive"))
      (node (ref "C55") (pin "1") (pinfunction "1_1") (pintype "passive"))
      (node (ref "C56") (pin "1") (pinfunction "1_1") (pintype "passive"))
      (node (ref "C57") (pin "1") (pinfunction "1_1") (pintype "passive"))
      (node (ref "C58") (pin "1") (pinfunction "1_1") (pintype "passive"))
      (node (ref "C59") (pin "1") (pinfunction "1_1") (pintype "passive"))
      (node (ref "C60") (pin "1") (pinfunction "1_1") (pintype "passive"))
      (node (ref "C61") (pin "1") (pinfunction "1_1") (pintype "passive"))
      (node (ref "C62") (pin "1") (pinfunction "1_1") (pintype "passive"))
      (node (ref "C63") (pin "1") (pinfunction "1_1") (pintype "passive"))
      (node (ref "C64") (pin "1") (pinfunction "1_1") (pintype "passive"))
      (node (ref "C65") (pin "1") (pinfunction "1_1") (pintype "passive"))
      (node (ref "C66") (pin "1") (pinfunction "1_1") (pintype "passive"))
      (node (ref "C67") (pin "1") (pinfunction "1_1") (pintype "passive"))
      (node (ref "C70") (pin "1") (pinfunction "1_1") (pintype "passive"))
      (node (ref "C71") (pin "1") (pinfunction "1_1") (pintype "passive"))
      (node (ref "C96") (pin "1") (pinfunction "1_1") (pintype "passive"))
      (node (ref "C97") (pin "1") (pinfunction "1_1") (pintype "passive"))
      (node (ref "DD11") (pin "14") (pinfunction "GNDIO_2_14") (pintype "passive"))
      (node (ref "DD11") (pin "24") (pinfunction "GNDA_24") (pintype "passive"))
      (node (ref "DD11") (pin "3") (pinfunction "GNDIO_1_3") (pintype "passive"))
      (node (ref "DD11") (pin "44") (pinfunction "GNDIO_3_44") (pintype "passive"))
      (node (ref "DD11") (pin "53") (pinfunction "GNDIO_4_53") (pintype "passive"))
      (node (ref "DD11") (pin "54") (pinfunction "TEST_54") (pintype "passive"))
      (node (ref "DD11") (pin "62") (pinfunction "GNDIO_5_62") (pintype "passive"))
      (node (ref "DD11") (pin "73") (pinfunction "GNDIO_6_73") (pintype "passive"))
      (node (ref "DD11") (pin "77") (pinfunction "GNDPAD_77") (pintype "passive"))
      (node (ref "DD12") (pin "14") (pinfunction "GNDIO_2_14") (pintype "passive"))
      (node (ref "DD12") (pin "24") (pinfunction "GNDA_24") (pintype "passive"))
      (node (ref "DD12") (pin "3") (pinfunction "GNDIO_1_3") (pintype "passive"))
      (node (ref "DD12") (pin "44") (pinfunction "GNDIO_3_44") (pintype "passive"))
      (node (ref "DD12") (pin "53") (pinfunction "GNDIO_4_53") (pintype "passive"))
      (node (ref "DD12") (pin "54") (pinfunction "TEST_54") (pintype "passive"))
      (node (ref "DD12") (pin "62") (pinfunction "GNDIO_5_62") (pintype "passive"))
      (node (ref "DD12") (pin "73") (pinfunction "GNDIO_6_73") (pintype "passive"))
      (node (ref "DD12") (pin "77") (pinfunction "GNDPAD_77") (pintype "passive"))
      (node (ref "R37") (pin "2") (pinfunction "2_2") (pintype "passive"))
      (node (ref "R38") (pin "2") (pinfunction "2_2") (pintype "passive"))
      (node (ref "R39") (pin "2") (pinfunction "2_2") (pintype "passive"))
      (node (ref "R40") (pin "2") (pinfunction "2_2") (pintype "passive"))
      (node (ref "R49") (pin "1") (pinfunction "1_1") (pintype "passive"))
      (node (ref "R50") (pin "1") (pinfunction "1_1") (pintype "passive"))
      (node (ref "R51") (pin "1") (pinfunction "1_1") (pintype "passive"))
      (node (ref "R52") (pin "1") (pinfunction "1_1") (pintype "passive"))
      (node (ref "X6") (pin "1") (pinfunction "1_1") (pintype "passive"))
      (node (ref "X6") (pin "10") (pinfunction "10_10") (pintype "passive"))
      (node (ref "X6") (pin "13") (pinfunction "13_13") (pintype "passive"))
      (node (ref "X6") (pin "16") (pinfunction "16_16") (pintype "passive"))
      (node (ref "X6") (pin "19") (pinfunction "19_19") (pintype "passive"))
      (node (ref "X6") (pin "23") (pinfunction "23_23") (pintype "passive"))
      (node (ref "X6") (pin "25") (pinfunction "25_25") (pintype "passive"))
      (node (ref "X6") (pin "27") (pinfunction "27_27") (pintype "passive"))
      (node (ref "X7") (pin "1") (pinfunction "1_1") (pintype "passive"))
      (node (ref "X7") (pin "10") (pinfunction "10_10") (pintype "passive"))
      (node (ref "X7") (pin "13") (pinfunction "13_13") (pintype "passive"))
      (node (ref "X7") (pin "16") (pinfunction "16_16") (pintype "passive"))
      (node (ref "X7") (pin "19") (pinfunction "19_19") (pintype "passive"))
      (node (ref "X7") (pin "23") (pinfunction "23_23") (pintype "passive"))
      (node (ref "X7") (pin "25") (pinfunction "25_25") (pintype "passive"))
      (node (ref "X7") (pin "27") (pinfunction "27_27") (pintype "passive"))
    )
    (net (code "77") (name "Net-(DD11-NRST)") (class "Default")
      (node (ref "C39") (pin "2") (pinfunction "2_2") (pintype "passive"))
      (node (ref "DD11") (pin "50") (pinfunction "NRST_50") (pintype "passive"))
      (node (ref "R41") (pin "1") (pinfunction "1_1") (pintype "passive"))
      (node (ref "R43") (pin "1") (pinfunction "1_1") (pintype "passive"))
    )
    (net (code "78") (name "Net-(DD11-PWM_IDLE_H)") (class "Default")
      (node (ref "DD11") (pin "59") (pinfunction "PWM_IDLE_H_59") (pintype "passive"))
      (node (ref "R37") (pin "1") (pinfunction "1_1") (pintype "passive"))
    )
    (net (code "79") (name "Net-(DD11-PWM_IDLE_L)") (class "Default")
      (node (ref "DD11") (pin "60") (pinfunction "PWM_IDLE_L_60") (pintype "passive"))
      (node (ref "R39") (pin "1") (pinfunction "1_1") (pintype "passive"))
    )
    (net (code "80") (name "Net-(DD11-VCCCORE_1)") (class "Default")
      (node (ref "C57") (pin "2") (pinfunction "2_2") (pintype "passive"))
      (node (ref "C58") (pin "2") (pinfunction "2_2") (pintype "passive"))
      (node (ref "C59") (pin "2") (pinfunction "2_2") (pintype "passive"))
      (node (ref "DD11") (pin "15") (pinfunction "VCCCORE_1_15") (pintype "passive"))
      (node (ref "DD11") (pin "45") (pinfunction "VCCCORE_2_45") (pintype "passive"))
      (node (ref "DD11") (pin "63") (pinfunction "VCCCORE_3_63") (pintype "passive"))
    )
    (net (code "81") (name "Net-(DD12-NRST)") (class "Default")
      (node (ref "C40") (pin "2") (pinfunction "2_2") (pintype "passive"))
      (node (ref "DD12") (pin "50") (pinfunction "NRST_50") (pintype "passive"))
      (node (ref "R42") (pin "1") (pinfunction "1_1") (pintype "passive"))
      (node (ref "R44") (pin "1") (pinfunction "1_1") (pintype "passive"))
    )
    (net (code "82") (name "Net-(DD12-PWM_IDLE_H)") (class "Default")
      (node (ref "DD12") (pin "59") (pinfunction "PWM_IDLE_H_59") (pintype "passive"))
      (node (ref "R38") (pin "1") (pinfunction "1_1") (pintype "passive"))
    )
    (net (code "83") (name "Net-(DD12-PWM_IDLE_L)") (class "Default")
      (node (ref "DD12") (pin "60") (pinfunction "PWM_IDLE_L_60") (pintype "passive"))
      (node (ref "R40") (pin "1") (pinfunction "1_1") (pintype "passive"))
    )
    (net (code "84") (name "Net-(DD12-VCCCORE_1)") (class "Default")
      (node (ref "C60") (pin "2") (pinfunction "2_2") (pintype "passive"))
      (node (ref "C61") (pin "2") (pinfunction "2_2") (pintype "passive"))
      (node (ref "C62") (pin "2") (pinfunction "2_2") (pintype "passive"))
      (node (ref "DD12") (pin "15") (pinfunction "VCCCORE_1_15") (pintype "passive"))
      (node (ref "DD12") (pin "45") (pinfunction "VCCCORE_2_45") (pintype "passive"))
      (node (ref "DD12") (pin "63") (pinfunction "VCCCORE_3_63") (pintype "passive"))
    )
    (net (code "85") (name "unconnected-(DD11-AENC_UX_NEG-Pad26)") (class "Default")
      (node (ref "DD11") (pin "26") (pinfunction "AENC_UX_NEG_26") (pintype "passive"))
    )
    (net (code "86") (name "unconnected-(DD11-AENC_UX_POS-Pad25)") (class "Default")
      (node (ref "DD11") (pin "25") (pinfunction "AENC_UX_POS_25") (pintype "passive"))
    )
    (net (code "87") (name "unconnected-(DD11-AENC_VN_NEG-Pad28)") (class "Default")
      (node (ref "DD11") (pin "28") (pinfunction "AENC_VN_NEG_28") (pintype "passive"))
    )
    (net (code "88") (name "unconnected-(DD11-AENC_VN_POS-Pad27)") (class "Default")
      (node (ref "DD11") (pin "27") (pinfunction "AENC_VN_POS_27") (pintype "passive"))
    )
    (net (code "89") (name "unconnected-(DD11-AENC_WY_NEG-Pad30)") (class "Default")
      (node (ref "DD11") (pin "30") (pinfunction "AENC_WY_NEG_30") (pintype "passive"))
    )
    (net (code "90") (name "unconnected-(DD11-AENC_WY_POS-Pad29)") (class "Default")
      (node (ref "DD11") (pin "29") (pinfunction "AENC_WY_POS_29") (pintype "passive"))
    )
    (net (code "91") (name "unconnected-(DD11-AGPI_A-Pad21)") (class "Default")
      (node (ref "DD11") (pin "21") (pinfunction "AGPI_A_21") (pintype "passive"))
    )
    (net (code "92") (name "unconnected-(DD11-AGPI_B-Pad22)") (class "Default")
      (node (ref "DD11") (pin "22") (pinfunction "AGPI_B_22") (pintype "passive"))
    )
    (net (code "93") (name "unconnected-(DD11-ENC_1N-Pad33)") (class "Default")
      (node (ref "DD11") (pin "33") (pinfunction "ENC_1N_33") (pintype "passive"))
    )
    (net (code "94") (name "unconnected-(DD11-ENC_2A-Pad64)") (class "Default")
      (node (ref "DD11") (pin "64") (pinfunction "ENC_2A_64") (pintype "passive"))
    )
    (net (code "95") (name "unconnected-(DD11-ENC_2B-Pad65)") (class "Default")
      (node (ref "DD11") (pin "65") (pinfunction "ENC_2B_65") (pintype "passive"))
    )
    (net (code "96") (name "unconnected-(DD11-ENC_2N-Pad66)") (class "Default")
      (node (ref "DD11") (pin "66") (pinfunction "ENC_2N_66") (pintype "passive"))
    )
    (net (code "97") (name "unconnected-(DD11-GPIO_0-Pad70)") (class "Default")
      (node (ref "DD11") (pin "70") (pinfunction "GPIO_0_70") (pintype "passive"))
    )
    (net (code "98") (name "unconnected-(DD11-GPIO_1-Pad71)") (class "Default")
      (node (ref "DD11") (pin "71") (pinfunction "GPIO_1_71") (pintype "passive"))
    )
    (net (code "99") (name "unconnected-(DD11-GPIO_2-Pad74)") (class "Default")
      (node (ref "DD11") (pin "74") (pinfunction "GPIO_2_74") (pintype "passive"))
    )
    (net (code "100") (name "unconnected-(DD11-GPIO_3-Pad75)") (class "Default")
      (node (ref "DD11") (pin "75") (pinfunction "GPIO_3_75") (pintype "passive"))
    )
    (net (code "101") (name "unconnected-(DD11-GPIO_4-Pad76)") (class "Default")
      (node (ref "DD11") (pin "76") (pinfunction "GPIO_4_76") (pintype "passive"))
    )
    (net (code "102") (name "unconnected-(DD11-GPIO_5-Pad1)") (class "Default")
      (node (ref "DD11") (pin "1") (pinfunction "GPIO_5_1") (pintype "passive"))
    )
    (net (code "103") (name "unconnected-(DD11-GPIO_6-Pad4)") (class "Default")
      (node (ref "DD11") (pin "4") (pinfunction "GPIO_6_4") (pintype "passive"))
    )
    (net (code "104") (name "unconnected-(DD11-GPIO_7-Pad5)") (class "Default")
      (node (ref "DD11") (pin "5") (pinfunction "GPIO_7_5") (pintype "passive"))
    )
    (net (code "105") (name "unconnected-(DD11-HALL_UX-Pad38)") (class "Default")
      (node (ref "DD11") (pin "38") (pinfunction "HALL_UX_38") (pintype "passive"))
    )
    (net (code "106") (name "unconnected-(DD11-HALL_V-Pad37)") (class "Default")
      (node (ref "DD11") (pin "37") (pinfunction "HALL_V_37") (pintype "passive"))
    )
    (net (code "107") (name "unconnected-(DD11-HALL_WY-Pad36)") (class "Default")
      (node (ref "DD11") (pin "36") (pinfunction "HALL_WY_36") (pintype "passive"))
    )
    (net (code "108") (name "unconnected-(DD11-PWM_I-Pad58)") (class "Default")
      (node (ref "DD11") (pin "58") (pinfunction "PWM_I_58") (pintype "passive"))
    )
    (net (code "109") (name "unconnected-(DD11-REF_SW_H-Pad68)") (class "Default")
      (node (ref "DD11") (pin "68") (pinfunction "REF_SW_H_68") (pintype "passive"))
    )
    (net (code "110") (name "unconnected-(DD11-REF_SW_L-Pad67)") (class "Default")
      (node (ref "DD11") (pin "67") (pinfunction "REF_SW_L_67") (pintype "passive"))
    )
    (net (code "111") (name "unconnected-(DD11-REF_SW_R-Pad69)") (class "Default")
      (node (ref "DD11") (pin "69") (pinfunction "REF_SW_R_69") (pintype "passive"))
    )
    (net (code "112") (name "unconnected-(DD12-AENC_UX_NEG-Pad26)") (class "Default")
      (node (ref "DD12") (pin "26") (pinfunction "AENC_UX_NEG_26") (pintype "passive"))
    )
    (net (code "113") (name "unconnected-(DD12-AENC_UX_POS-Pad25)") (class "Default")
      (node (ref "DD12") (pin "25") (pinfunction "AENC_UX_POS_25") (pintype "passive"))
    )
    (net (code "114") (name "unconnected-(DD12-AENC_VN_NEG-Pad28)") (class "Default")
      (node (ref "DD12") (pin "28") (pinfunction "AENC_VN_NEG_28") (pintype "passive"))
    )
    (net (code "115") (name "unconnected-(DD12-AENC_VN_POS-Pad27)") (class "Default")
      (node (ref "DD12") (pin "27") (pinfunction "AENC_VN_POS_27") (pintype "passive"))
    )
    (net (code "116") (name "unconnected-(DD12-AENC_WY_NEG-Pad30)") (class "Default")
      (node (ref "DD12") (pin "30") (pinfunction "AENC_WY_NEG_30") (pintype "passive"))
    )
    (net (code "117") (name "unconnected-(DD12-AENC_WY_POS-Pad29)") (class "Default")
      (node (ref "DD12") (pin "29") (pinfunction "AENC_WY_POS_29") (pintype "passive"))
    )
    (net (code "118") (name "unconnected-(DD12-AGPI_A-Pad21)") (class "Default")
      (node (ref "DD12") (pin "21") (pinfunction "AGPI_A_21") (pintype "passive"))
    )
    (net (code "119") (name "unconnected-(DD12-AGPI_B-Pad22)") (class "Default")
      (node (ref "DD12") (pin "22") (pinfunction "AGPI_B_22") (pintype "passive"))
    )
    (net (code "120") (name "unconnected-(DD12-ENC_1N-Pad33)") (class "Default")
      (node (ref "DD12") (pin "33") (pinfunction "ENC_1N_33") (pintype "passive"))
    )
    (net (code "121") (name "unconnected-(DD12-ENC_2A-Pad64)") (class "Default")
      (node (ref "DD12") (pin "64") (pinfunction "ENC_2A_64") (pintype "passive"))
    )
    (net (code "122") (name "unconnected-(DD12-ENC_2B-Pad65)") (class "Default")
      (node (ref "DD12") (pin "65") (pinfunction "ENC_2B_65") (pintype "passive"))
    )
    (net (code "123") (name "unconnected-(DD12-ENC_2N-Pad66)") (class "Default")
      (node (ref "DD12") (pin "66") (pinfunction "ENC_2N_66") (pintype "passive"))
    )
    (net (code "124") (name "unconnected-(DD12-GPIO_0-Pad70)") (class "Default")
      (node (ref "DD12") (pin "70") (pinfunction "GPIO_0_70") (pintype "passive"))
    )
    (net (code "125") (name "unconnected-(DD12-GPIO_1-Pad71)") (class "Default")
      (node (ref "DD12") (pin "71") (pinfunction "GPIO_1_71") (pintype "passive"))
    )
    (net (code "126") (name "unconnected-(DD12-GPIO_2-Pad74)") (class "Default")
      (node (ref "DD12") (pin "74") (pinfunction "GPIO_2_74") (pintype "passive"))
    )
    (net (code "127") (name "unconnected-(DD12-GPIO_3-Pad75)") (class "Default")
      (node (ref "DD12") (pin "75") (pinfunction "GPIO_3_75") (pintype "passive"))
    )
    (net (code "128") (name "unconnected-(DD12-GPIO_4-Pad76)") (class "Default")
      (node (ref "DD12") (pin "76") (pinfunction "GPIO_4_76") (pintype "passive"))
    )
    (net (code "129") (name "unconnected-(DD12-GPIO_5-Pad1)") (class "Default")
      (node (ref "DD12") (pin "1") (pinfunction "GPIO_5_1") (pintype "passive"))
    )
    (net (code "130") (name "unconnected-(DD12-GPIO_6-Pad4)") (class "Default")
      (node (ref "DD12") (pin "4") (pinfunction "GPIO_6_4") (pintype "passive"))
    )
    (net (code "131") (name "unconnected-(DD12-GPIO_7-Pad5)") (class "Default")
      (node (ref "DD12") (pin "5") (pinfunction "GPIO_7_5") (pintype "passive"))
    )
    (net (code "132") (name "unconnected-(DD12-HALL_UX-Pad38)") (class "Default")
      (node (ref "DD12") (pin "38") (pinfunction "HALL_UX_38") (pintype "passive"))
    )
    (net (code "133") (name "unconnected-(DD12-HALL_V-Pad37)") (class "Default")
      (node (ref "DD12") (pin "37") (pinfunction "HALL_V_37") (pintype "passive"))
    )
    (net (code "134") (name "unconnected-(DD12-HALL_WY-Pad36)") (class "Default")
      (node (ref "DD12") (pin "36") (pinfunction "HALL_WY_36") (pintype "passive"))
    )
    (net (code "135") (name "unconnected-(DD12-PWM_I-Pad58)") (class "Default")
      (node (ref "DD12") (pin "58") (pinfunction "PWM_I_58") (pintype "passive"))
    )
    (net (code "136") (name "unconnected-(DD12-REF_SW_H-Pad68)") (class "Default")
      (node (ref "DD12") (pin "68") (pinfunction "REF_SW_H_68") (pintype "passive"))
    )
    (net (code "137") (name "unconnected-(DD12-REF_SW_L-Pad67)") (class "Default")
      (node (ref "DD12") (pin "67") (pinfunction "REF_SW_L_67") (pintype "passive"))
    )
    (net (code "138") (name "unconnected-(DD12-REF_SW_R-Pad69)") (class "Default")
      (node (ref "DD12") (pin "69") (pinfunction "REF_SW_R_69") (pintype "passive"))
    )
  )
)
